# control.net
KiCad netlist of a schematic drawn in Altium Designer
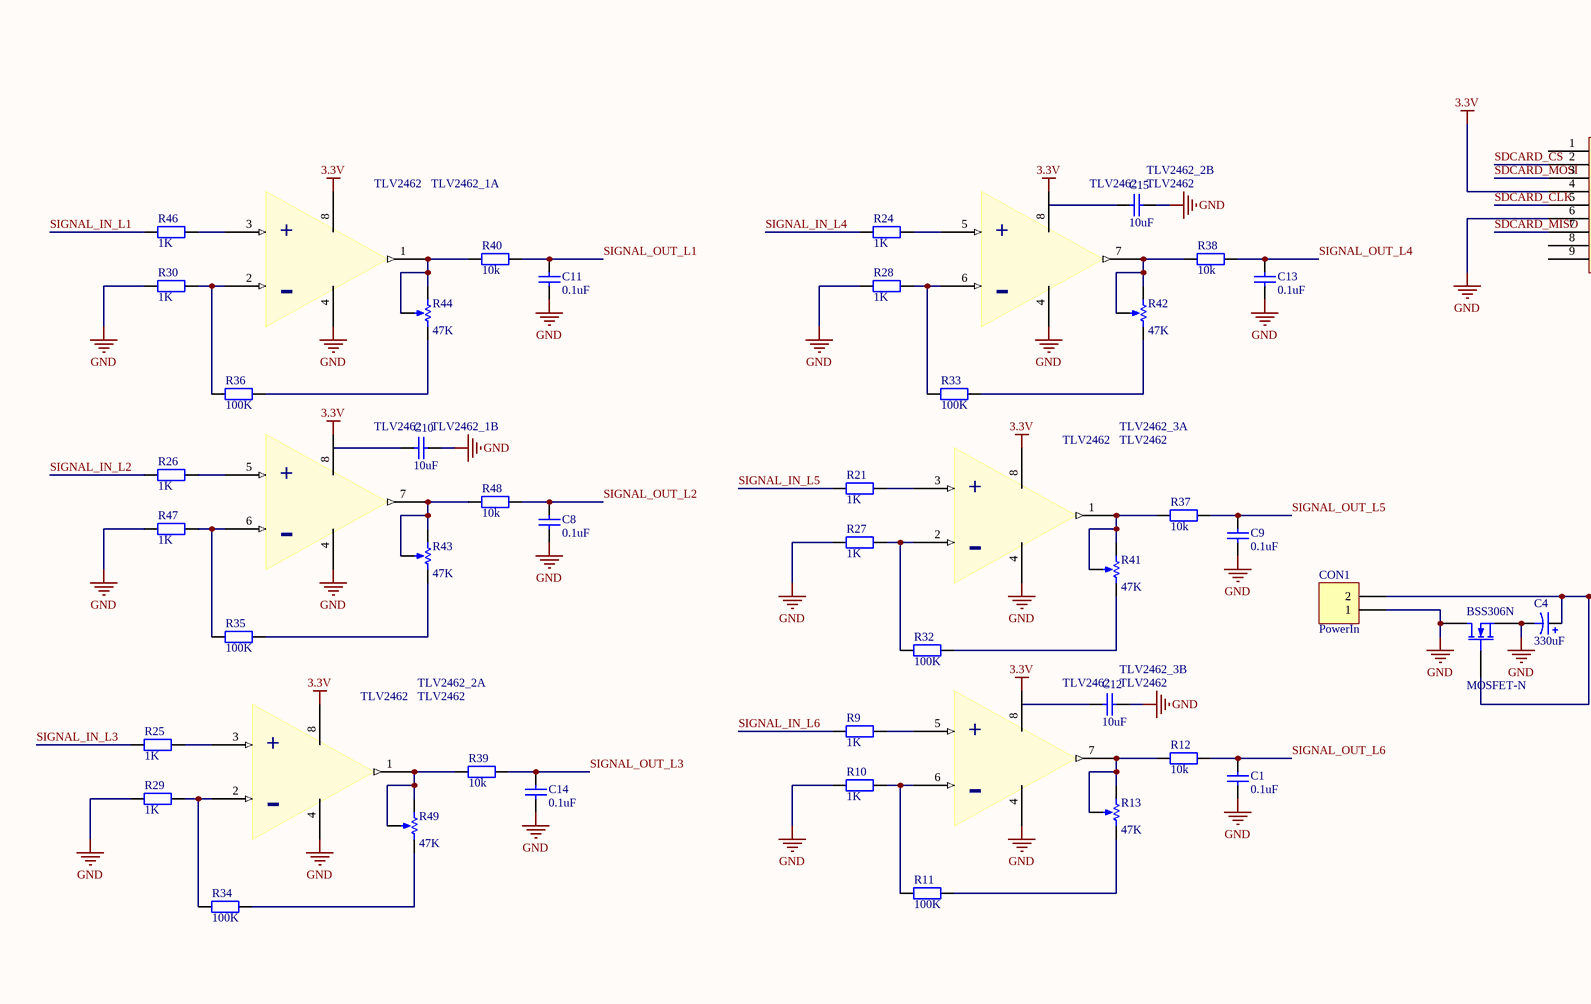
[diagram p0: control.SchDoc, top left]
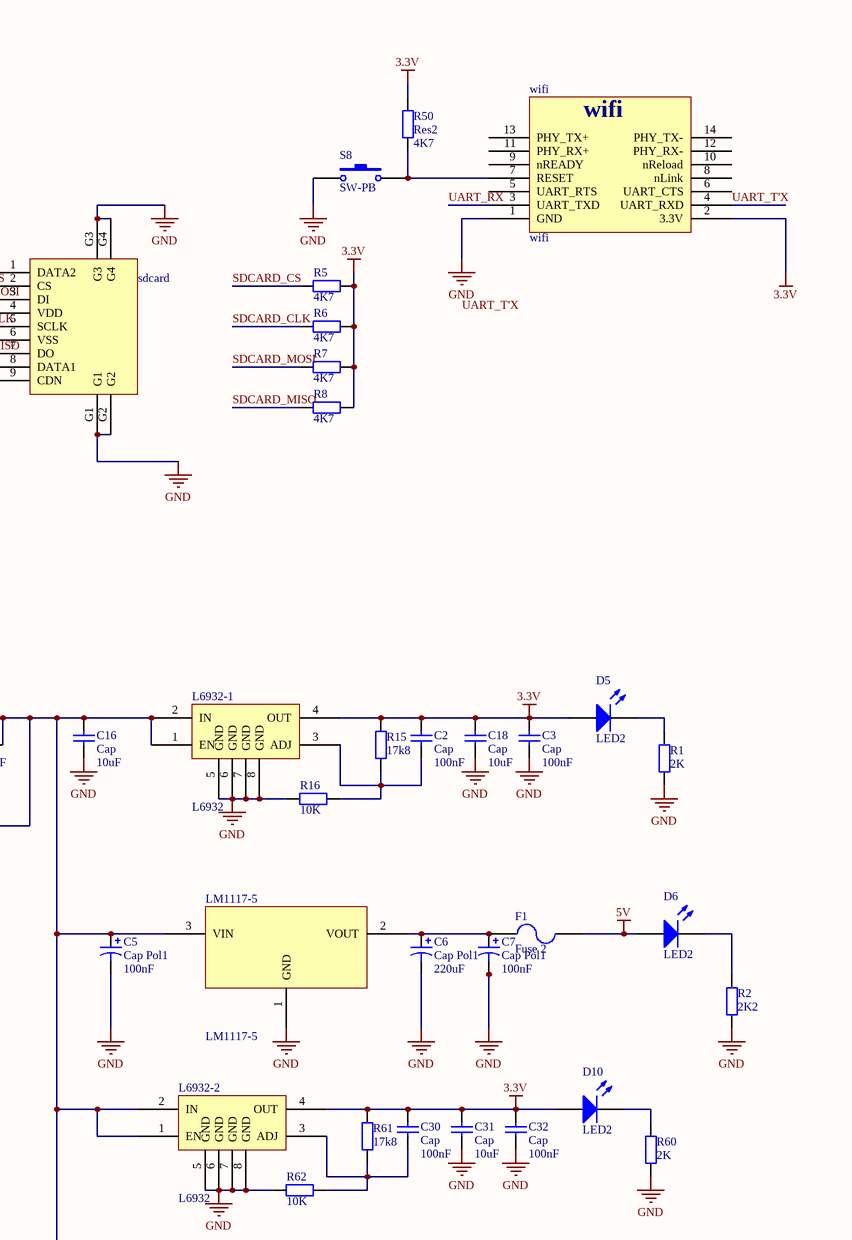
[diagram p1: control.SchDoc, top right]
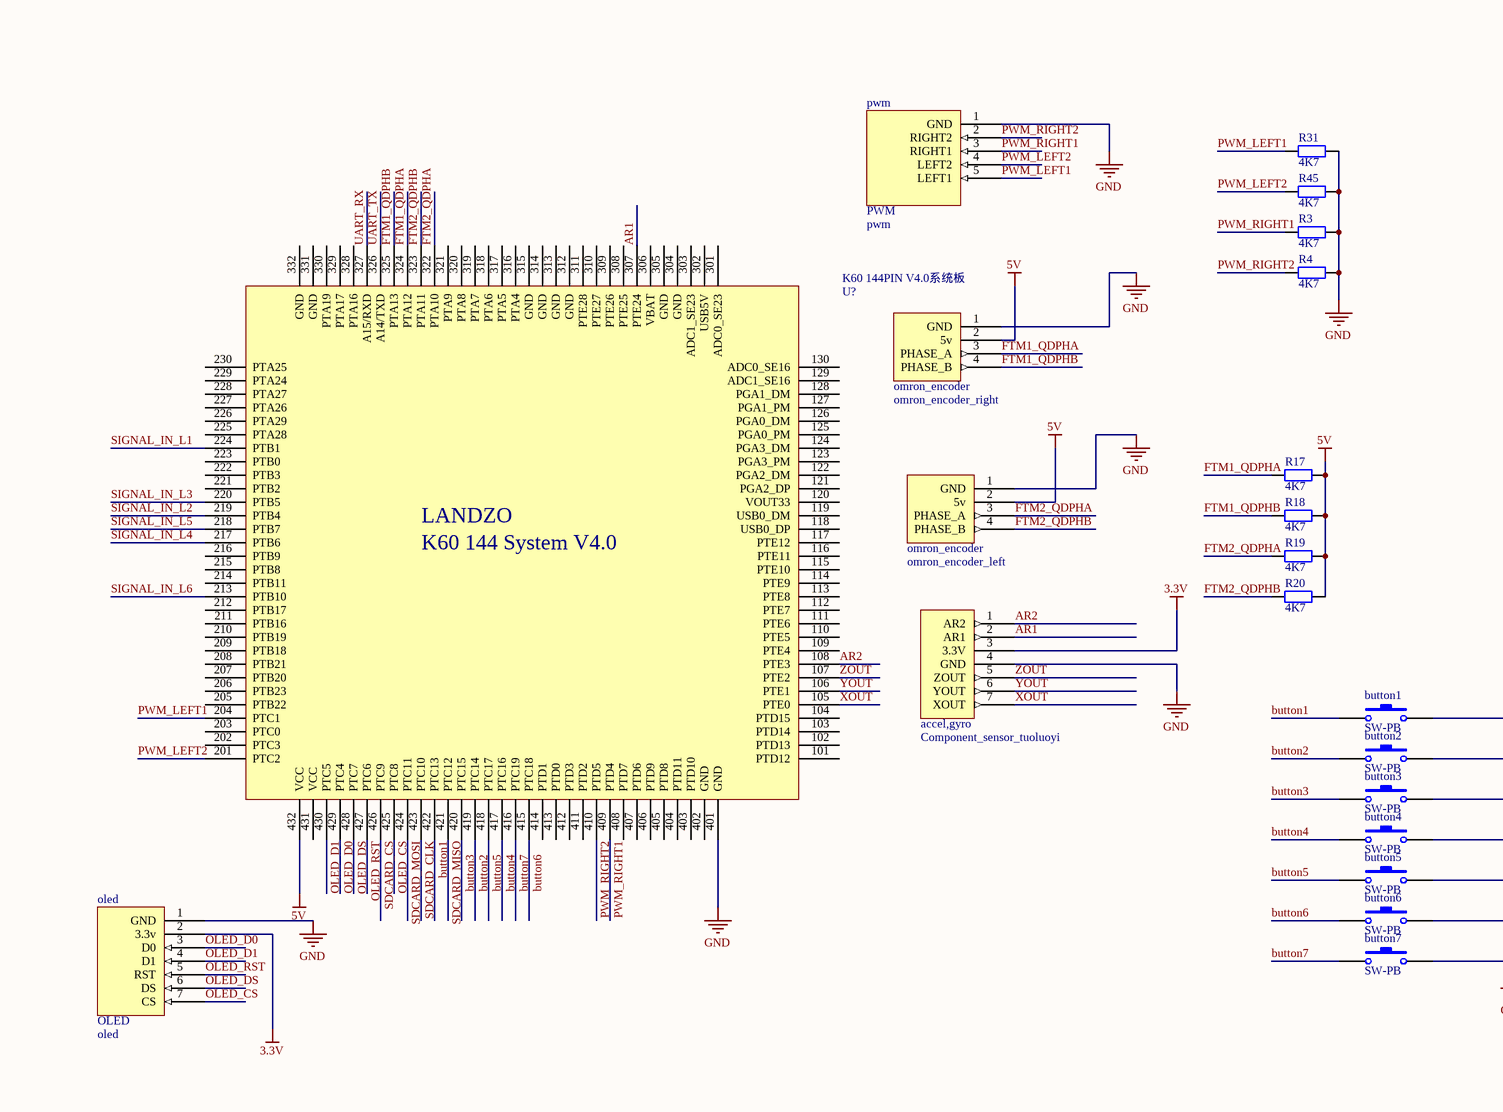
[diagram p2: control.SchDoc, bottom left]
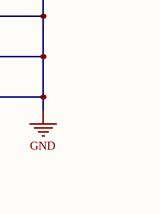
[diagram p3: control.SchDoc, bottom right]

(export (version "E")
  (design (tool "Eeschema 10.0.6"))
  (components
    (comp (ref "BSS306N")
      (value "MOSFET-N")
      (footprint "E3")
      (description "N-Channel MOSFET")
      (fields (field (name "PUBLISHER") "Altium Limited"))
      (libsource (lib "Miscellaneous Devices") (part "MOSFET-N"))
    )
    (comp (ref "button1")
      (value "SW-PB")
      (footprint "SPST-2")
      (description "Switch")
      (fields (field (name "PUBLISHER") "Altium Limited"))
      (libsource (lib "Miscellaneous Devices") (part "SW-PB"))
    )
    (comp (ref "button2")
      (value "SW-PB")
      (footprint "SPST-2")
      (description "Switch")
      (fields (field (name "PUBLISHER") "Altium Limited"))
      (libsource (lib "Miscellaneous Devices") (part "SW-PB"))
    )
    (comp (ref "button3")
      (value "SW-PB")
      (footprint "SPST-2")
      (description "Switch")
      (fields (field (name "PUBLISHER") "Altium Limited"))
      (libsource (lib "Miscellaneous Devices") (part "SW-PB"))
    )
    (comp (ref "button4")
      (value "SW-PB")
      (footprint "SPST-2")
      (description "Switch")
      (fields (field (name "PUBLISHER") "Altium Limited"))
      (libsource (lib "Miscellaneous Devices") (part "SW-PB"))
    )
    (comp (ref "button5")
      (value "SW-PB")
      (footprint "SPST-2")
      (description "Switch")
      (fields (field (name "PUBLISHER") "Altium Limited"))
      (libsource (lib "Miscellaneous Devices") (part "SW-PB"))
    )
    (comp (ref "button6")
      (value "SW-PB")
      (footprint "SPST-2")
      (description "Switch")
      (fields (field (name "PUBLISHER") "Altium Limited"))
      (libsource (lib "Miscellaneous Devices") (part "SW-PB"))
    )
    (comp (ref "button7")
      (value "SW-PB")
      (footprint "SPST-2")
      (description "Switch")
      (fields (field (name "PUBLISHER") "Altium Limited"))
      (libsource (lib "Miscellaneous Devices") (part "SW-PB"))
    )
    (comp (ref "C1")
      (value "0.1uF")
      (footprint "6-0805_M")
      (description "Capacitor")
      (fields (field (name "Comment") "Cap") (field (name "PUBLISHER") "Altium Limited"))
      (libsource (lib "Miscellaneous Devices") (part "Cap"))
    )
    (comp (ref "C2")
      (value "Cap")
      (footprint "6-0805_M")
      (description "Capacitor")
      (fields (field (name "ALTIUM_VALUE") "100nF") (field (name "PUBLISHER") "Altium Limited"))
      (libsource (lib "Miscellaneous Devices") (part "Cap"))
    )
    (comp (ref "C3")
      (value "Cap")
      (footprint "6-0805_M")
      (description "Capacitor")
      (fields (field (name "ALTIUM_VALUE") "100nF") (field (name "PUBLISHER") "Altium Limited"))
      (libsource (lib "Miscellaneous Devices") (part "Cap"))
    )
    (comp (ref "C4")
      (value "330uF")
      (footprint "RB7.6-15")
      (description "Polarized Capacitor (Radial)")
      (fields (field (name "Comment") "Cap Pol1") (field (name "PUBLISHER") "Altium Limited"))
      (libsource (lib "Miscellaneous Devices") (part "Cap Pol1"))
    )
    (comp (ref "C5")
      (value "Cap Pol1")
      (footprint "RAD-0.1")
      (description "Polarized Capacitor (Radial)")
      (fields (field (name "ALTIUM_VALUE") "100nF") (field (name "PUBLISHER") "Altium Limited"))
      (libsource (lib "Miscellaneous Devices") (part "Cap Pol1"))
    )
    (comp (ref "C6")
      (value "Cap Pol1")
      (footprint "RAD-0.1")
      (description "Polarized Capacitor (Radial)")
      (fields (field (name "ALTIUM_VALUE") "220uF") (field (name "PUBLISHER") "Altium Limited"))
      (libsource (lib "Miscellaneous Devices") (part "Cap Pol1"))
    )
    (comp (ref "C7")
      (value "Cap Pol1")
      (footprint "RAD-0.1")
      (description "Polarized Capacitor (Radial)")
      (fields (field (name "ALTIUM_VALUE") "100nF") (field (name "PUBLISHER") "Altium Limited"))
      (libsource (lib "Miscellaneous Devices") (part "Cap Pol1"))
    )
    (comp (ref "C8")
      (value "0.1uF")
      (footprint "6-0805_M")
      (description "Capacitor")
      (fields (field (name "Comment") "Cap") (field (name "PUBLISHER") "Altium Limited"))
      (libsource (lib "Miscellaneous Devices") (part "Cap"))
    )
    (comp (ref "C9")
      (value "0.1uF")
      (footprint "6-0805_M")
      (description "Capacitor")
      (fields (field (name "Comment") "Cap") (field (name "PUBLISHER") "Altium Limited"))
      (libsource (lib "Miscellaneous Devices") (part "Cap"))
    )
    (comp (ref "C10")
      (value "10uF")
      (footprint "6-0805_M")
      (description "Capacitor")
      (fields (field (name "Comment") "Cap") (field (name "PUBLISHER") "Altium Limited"))
      (libsource (lib "Miscellaneous Devices") (part "Cap"))
    )
    (comp (ref "C11")
      (value "0.1uF")
      (footprint "6-0805_M")
      (description "Capacitor")
      (fields (field (name "Comment") "Cap") (field (name "PUBLISHER") "Altium Limited"))
      (libsource (lib "Miscellaneous Devices") (part "Cap"))
    )
    (comp (ref "C12")
      (value "10uF")
      (footprint "6-0805_M")
      (description "Capacitor")
      (fields (field (name "Comment") "Cap") (field (name "PUBLISHER") "Altium Limited"))
      (libsource (lib "Miscellaneous Devices") (part "Cap"))
    )
    (comp (ref "C13")
      (value "0.1uF")
      (footprint "6-0805_M")
      (description "Capacitor")
      (fields (field (name "Comment") "Cap") (field (name "PUBLISHER") "Altium Limited"))
      (libsource (lib "Miscellaneous Devices") (part "Cap"))
    )
    (comp (ref "C14")
      (value "0.1uF")
      (footprint "6-0805_M")
      (description "Capacitor")
      (fields (field (name "Comment") "Cap") (field (name "PUBLISHER") "Altium Limited"))
      (libsource (lib "Miscellaneous Devices") (part "Cap"))
    )
    (comp (ref "C15")
      (value "10uF")
      (footprint "6-0805_M")
      (description "Capacitor")
      (fields (field (name "Comment") "Cap") (field (name "PUBLISHER") "Altium Limited"))
      (libsource (lib "Miscellaneous Devices") (part "Cap"))
    )
    (comp (ref "C16")
      (value "Cap")
      (footprint "6-0805_M")
      (description "Capacitor")
      (fields (field (name "ALTIUM_VALUE") "10uF") (field (name "PUBLISHER") "Altium Limited"))
      (libsource (lib "Miscellaneous Devices") (part "Cap"))
    )
    (comp (ref "C18")
      (value "Cap")
      (footprint "6-0805_M")
      (description "Capacitor")
      (fields (field (name "ALTIUM_VALUE") "10uF") (field (name "PUBLISHER") "Altium Limited"))
      (libsource (lib "Miscellaneous Devices") (part "Cap"))
    )
    (comp (ref "C30")
      (value "Cap")
      (footprint "6-0805_M")
      (description "Capacitor")
      (fields (field (name "ALTIUM_VALUE") "100nF") (field (name "PUBLISHER") "Altium Limited"))
      (libsource (lib "Miscellaneous Devices") (part "Cap"))
    )
    (comp (ref "C31")
      (value "Cap")
      (footprint "6-0805_M")
      (description "Capacitor")
      (fields (field (name "ALTIUM_VALUE") "10uF") (field (name "PUBLISHER") "Altium Limited"))
      (libsource (lib "Miscellaneous Devices") (part "Cap"))
    )
    (comp (ref "C32")
      (value "Cap")
      (footprint "6-0805_M")
      (description "Capacitor")
      (fields (field (name "ALTIUM_VALUE") "100nF") (field (name "PUBLISHER") "Altium Limited"))
      (libsource (lib "Miscellaneous Devices") (part "Cap"))
    )
    (comp (ref "CON1")
      (value "PowerIn")
      (description "Header, 2-Pin")
      (fields (field (name "PUBLISHER") "Altium Limited"))
      (libsource (lib "Miscellaneous Connectors") (part "Header 2"))
    )
    (comp (ref "D5")
      (value "LED2")
      (footprint "6-0805_M")
      (description "Typical RED, GREEN, YELLOW, AMBER GaAs LED")
      (fields (field (name "PUBLISHER") "Altium Limited"))
      (libsource (lib "Miscellaneous Devices") (part "LED2"))
    )
    (comp (ref "D6")
      (value "LED2")
      (footprint "6-0805_M")
      (description "Typical RED, GREEN, YELLOW, AMBER GaAs LED")
      (fields (field (name "PUBLISHER") "Altium Limited"))
      (libsource (lib "Miscellaneous Devices") (part "LED2"))
    )
    (comp (ref "D10")
      (value "LED2")
      (footprint "6-0805_M")
      (description "Typical RED, GREEN, YELLOW, AMBER GaAs LED")
      (fields (field (name "PUBLISHER") "Altium Limited"))
      (libsource (lib "Miscellaneous Devices") (part "LED2"))
    )
    (comp (ref "F1")
      (value "Fuse 2")
      (footprint "PIN-W2/E2.8")
      (description "Fuse")
      (fields (field (name "PUBLISHER") "Altium Limited"))
      (libsource (lib "Miscellaneous Devices") (part "Fuse 2"))
    )
    (comp (ref "K60 144PIN V4.0系统板")
      (value "U?")
      (footprint "K60_Board")
      (libsource (lib "最小系统板K60P144-V4.0") (part "K60 144PIN V4.0系统板"))
    )
    (comp (ref "L6932-1")
      (value "L6932")
      (footprint "L6932")
      (libsource (lib "Schlib_k60_core") (part "L6932"))
    )
    (comp (ref "L6932-2")
      (value "L6932")
      (footprint "L6932")
      (libsource (lib "Schlib_k60_core") (part "L6932"))
    )
    (comp (ref "LM1117-5")
      (value "LM1117-5")
      (footprint "SOT223_M")
      (libsource (lib "Schlib_k60_core") (part "LM1117-5"))
    )
    (comp (ref "oled") (value "oled") (footprint "HDR1X7H") (libsource (lib "Schlib_k60_core") (part "oled")))
    (comp (ref "omron_encoder_left")
      (value "omron_encoder")
      (footprint "HDR1X4H")
      (libsource (lib "Schlib_k60_core") (part "omron_encoder"))
    )
    (comp (ref "omron_encoder_right")
      (value "omron_encoder")
      (footprint "HDR1X4")
      (libsource (lib "Schlib_k60_core") (part "omron_encoder"))
    )
    (comp (ref "pwm") (value "pwm") (footprint "HDR1X5H") (libsource (lib "Schlib_k60_core") (part "pwm")))
    (comp (ref "R1")
      (value "2K")
      (footprint "6-0805_M")
      (description "Resistor")
      (fields (field (name "Comment") "Res2") (field (name "PUBLISHER") "Altium Limited"))
      (libsource (lib "") (part "Res2_1"))
    )
    (comp (ref "R2")
      (value "2K2")
      (footprint "6-0805_M")
      (description "Resistor")
      (fields (field (name "Comment") "Res2") (field (name "PUBLISHER") "Altium Limited"))
      (libsource (lib "") (part "Res2_1"))
    )
    (comp (ref "R3")
      (value "4K7")
      (footprint "6-0805_M")
      (description "Resistor")
      (fields (field (name "Comment") "Res2") (field (name "PUBLISHER") "Altium Limited"))
      (libsource (lib "Miscellaneous Devices") (part "Res2"))
    )
    (comp (ref "R4")
      (value "4K7")
      (footprint "6-0805_M")
      (description "Resistor")
      (fields (field (name "Comment") "Res2") (field (name "PUBLISHER") "Altium Limited"))
      (libsource (lib "Miscellaneous Devices") (part "Res2"))
    )
    (comp (ref "R5")
      (value "4K7")
      (footprint "6-0805_M")
      (description "Resistor")
      (fields (field (name "Comment") "Res2") (field (name "PUBLISHER") "Altium Limited"))
      (libsource (lib "Miscellaneous Devices") (part "Res2"))
    )
    (comp (ref "R6")
      (value "4K7")
      (footprint "6-0805_M")
      (description "Resistor")
      (fields (field (name "Comment") "Res2") (field (name "PUBLISHER") "Altium Limited"))
      (libsource (lib "Miscellaneous Devices") (part "Res2"))
    )
    (comp (ref "R7")
      (value "4K7")
      (footprint "6-0805_M")
      (description "Resistor")
      (fields (field (name "Comment") "Res2") (field (name "PUBLISHER") "Altium Limited"))
      (libsource (lib "Miscellaneous Devices") (part "Res2"))
    )
    (comp (ref "R8")
      (value "4K7")
      (footprint "6-0805_M")
      (description "Resistor")
      (fields (field (name "Comment") "Res2") (field (name "PUBLISHER") "Altium Limited"))
      (libsource (lib "Miscellaneous Devices") (part "Res2"))
    )
    (comp (ref "R9")
      (value "1K")
      (footprint "6-0805_M")
      (description "Resistor")
      (fields (field (name "Comment") "Res2") (field (name "PUBLISHER") "Altium Limited"))
      (libsource (lib "Miscellaneous Devices") (part "Res2"))
    )
    (comp (ref "R10")
      (value "1K")
      (footprint "6-0805_M")
      (description "Resistor")
      (fields (field (name "Comment") "Res2") (field (name "PUBLISHER") "Altium Limited"))
      (libsource (lib "Miscellaneous Devices") (part "Res2"))
    )
    (comp (ref "R11")
      (value "100K")
      (footprint "6-0805_M")
      (description "Resistor")
      (fields (field (name "Comment") "Res2") (field (name "PUBLISHER") "Altium Limited"))
      (libsource (lib "Miscellaneous Devices") (part "Res2"))
    )
    (comp (ref "R12")
      (value "10k")
      (footprint "6-0805_M")
      (description "Resistor")
      (fields (field (name "Comment") "Res2") (field (name "PUBLISHER") "Altium Limited"))
      (libsource (lib "Miscellaneous Devices") (part "Res2"))
    )
    (comp (ref "R13")
      (value "47K")
      (footprint "VR5")
      (description "Potentiometer")
      (fields (field (name "Comment") "R4") (field (name "PUBLISHER") "Altium Limited"))
      (libsource (lib "Miscellaneous Devices") (part "RPot"))
    )
    (comp (ref "R15")
      (value "17k8")
      (footprint "6-0805_M")
      (description "Resistor")
      (fields (field (name "Comment") "Res2") (field (name "PUBLISHER") "Altium Limited"))
      (libsource (lib "") (part "Res2_1"))
    )
    (comp (ref "R16")
      (value "10K")
      (footprint "6-0805_M")
      (description "Resistor")
      (fields (field (name "Comment") "Res2") (field (name "PUBLISHER") "Altium Limited"))
      (libsource (lib "Miscellaneous Devices") (part "Res2"))
    )
    (comp (ref "R17")
      (value "4K7")
      (footprint "6-0805_M")
      (description "Resistor")
      (fields (field (name "Comment") "Res2") (field (name "PUBLISHER") "Altium Limited"))
      (libsource (lib "Miscellaneous Devices") (part "Res2"))
    )
    (comp (ref "R18")
      (value "4K7")
      (footprint "6-0805_M")
      (description "Resistor")
      (fields (field (name "Comment") "Res2") (field (name "PUBLISHER") "Altium Limited"))
      (libsource (lib "Miscellaneous Devices") (part "Res2"))
    )
    (comp (ref "R19")
      (value "4K7")
      (footprint "6-0805_M")
      (description "Resistor")
      (fields (field (name "Comment") "Res2") (field (name "PUBLISHER") "Altium Limited"))
      (libsource (lib "Miscellaneous Devices") (part "Res2"))
    )
    (comp (ref "R20")
      (value "4K7")
      (footprint "6-0805_M")
      (description "Resistor")
      (fields (field (name "Comment") "Res2") (field (name "PUBLISHER") "Altium Limited"))
      (libsource (lib "Miscellaneous Devices") (part "Res2"))
    )
    (comp (ref "R21")
      (value "1K")
      (footprint "6-0805_M")
      (description "Resistor")
      (fields (field (name "Comment") "Res2") (field (name "PUBLISHER") "Altium Limited"))
      (libsource (lib "Miscellaneous Devices") (part "Res2"))
    )
    (comp (ref "R24")
      (value "1K")
      (footprint "6-0805_M")
      (description "Resistor")
      (fields (field (name "Comment") "Res2") (field (name "PUBLISHER") "Altium Limited"))
      (libsource (lib "Miscellaneous Devices") (part "Res2"))
    )
    (comp (ref "R25")
      (value "1K")
      (footprint "6-0805_M")
      (description "Resistor")
      (fields (field (name "Comment") "Res2") (field (name "PUBLISHER") "Altium Limited"))
      (libsource (lib "Miscellaneous Devices") (part "Res2"))
    )
    (comp (ref "R26")
      (value "1K")
      (footprint "6-0805_M")
      (description "Resistor")
      (fields (field (name "Comment") "Res2") (field (name "PUBLISHER") "Altium Limited"))
      (libsource (lib "Miscellaneous Devices") (part "Res2"))
    )
    (comp (ref "R27")
      (value "1K")
      (footprint "6-0805_M")
      (description "Resistor")
      (fields (field (name "Comment") "Res2") (field (name "PUBLISHER") "Altium Limited"))
      (libsource (lib "Miscellaneous Devices") (part "Res2"))
    )
    (comp (ref "R28")
      (value "1K")
      (footprint "6-0805_M")
      (description "Resistor")
      (fields (field (name "Comment") "Res2") (field (name "PUBLISHER") "Altium Limited"))
      (libsource (lib "Miscellaneous Devices") (part "Res2"))
    )
    (comp (ref "R29")
      (value "1K")
      (footprint "6-0805_M")
      (description "Resistor")
      (fields (field (name "Comment") "Res2") (field (name "PUBLISHER") "Altium Limited"))
      (libsource (lib "Miscellaneous Devices") (part "Res2"))
    )
    (comp (ref "R30")
      (value "1K")
      (footprint "6-0805_M")
      (description "Resistor")
      (fields (field (name "Comment") "Res2") (field (name "PUBLISHER") "Altium Limited"))
      (libsource (lib "Miscellaneous Devices") (part "Res2"))
    )
    (comp (ref "R31")
      (value "4K7")
      (footprint "6-0805_M")
      (description "Resistor")
      (fields (field (name "Comment") "Res2") (field (name "PUBLISHER") "Altium Limited"))
      (libsource (lib "Miscellaneous Devices") (part "Res2"))
    )
    (comp (ref "R32")
      (value "100K")
      (footprint "6-0805_M")
      (description "Resistor")
      (fields (field (name "Comment") "Res2") (field (name "PUBLISHER") "Altium Limited"))
      (libsource (lib "Miscellaneous Devices") (part "Res2"))
    )
    (comp (ref "R33")
      (value "100K")
      (footprint "6-0805_M")
      (description "Resistor")
      (fields (field (name "Comment") "Res2") (field (name "PUBLISHER") "Altium Limited"))
      (libsource (lib "Miscellaneous Devices") (part "Res2"))
    )
    (comp (ref "R34")
      (value "100K")
      (footprint "6-0805_M")
      (description "Resistor")
      (fields (field (name "Comment") "Res2") (field (name "PUBLISHER") "Altium Limited"))
      (libsource (lib "Miscellaneous Devices") (part "Res2"))
    )
    (comp (ref "R35")
      (value "100K")
      (footprint "6-0805_M")
      (description "Resistor")
      (fields (field (name "Comment") "Res2") (field (name "PUBLISHER") "Altium Limited"))
      (libsource (lib "Miscellaneous Devices") (part "Res2"))
    )
    (comp (ref "R36")
      (value "100K")
      (footprint "6-0805_M")
      (description "Resistor")
      (fields (field (name "Comment") "Res2") (field (name "PUBLISHER") "Altium Limited"))
      (libsource (lib "Miscellaneous Devices") (part "Res2"))
    )
    (comp (ref "R37")
      (value "10k")
      (footprint "6-0805_M")
      (description "Resistor")
      (fields (field (name "Comment") "Res2") (field (name "PUBLISHER") "Altium Limited"))
      (libsource (lib "Miscellaneous Devices") (part "Res2"))
    )
    (comp (ref "R38")
      (value "10k")
      (footprint "6-0805_M")
      (description "Resistor")
      (fields (field (name "Comment") "Res2") (field (name "PUBLISHER") "Altium Limited"))
      (libsource (lib "Miscellaneous Devices") (part "Res2"))
    )
    (comp (ref "R39")
      (value "10k")
      (footprint "6-0805_M")
      (description "Resistor")
      (fields (field (name "Comment") "Res2") (field (name "PUBLISHER") "Altium Limited"))
      (libsource (lib "Miscellaneous Devices") (part "Res2"))
    )
    (comp (ref "R40")
      (value "10k")
      (footprint "6-0805_M")
      (description "Resistor")
      (fields (field (name "Comment") "Res2") (field (name "PUBLISHER") "Altium Limited"))
      (libsource (lib "Miscellaneous Devices") (part "Res2"))
    )
    (comp (ref "R41")
      (value "47K")
      (footprint "VR5")
      (description "Potentiometer")
      (fields (field (name "Comment") "R4") (field (name "PUBLISHER") "Altium Limited"))
      (libsource (lib "Miscellaneous Devices") (part "RPot"))
    )
    (comp (ref "R42")
      (value "47K")
      (footprint "VR5")
      (description "Potentiometer")
      (fields (field (name "Comment") "R4") (field (name "PUBLISHER") "Altium Limited"))
      (libsource (lib "Miscellaneous Devices") (part "RPot"))
    )
    (comp (ref "R43")
      (value "47K")
      (footprint "VR5")
      (description "Potentiometer")
      (fields (field (name "Comment") "R4") (field (name "PUBLISHER") "Altium Limited"))
      (libsource (lib "Miscellaneous Devices") (part "RPot"))
    )
    (comp (ref "R44")
      (value "47K")
      (footprint "VR5")
      (description "Potentiometer")
      (fields (field (name "Comment") "R4") (field (name "PUBLISHER") "Altium Limited"))
      (libsource (lib "Miscellaneous Devices") (part "RPot"))
    )
    (comp (ref "R45")
      (value "4K7")
      (footprint "6-0805_M")
      (description "Resistor")
      (fields (field (name "Comment") "Res2") (field (name "PUBLISHER") "Altium Limited"))
      (libsource (lib "Miscellaneous Devices") (part "Res2"))
    )
    (comp (ref "R46")
      (value "1K")
      (footprint "6-0805_M")
      (description "Resistor")
      (fields (field (name "Comment") "Res2") (field (name "PUBLISHER") "Altium Limited"))
      (libsource (lib "Miscellaneous Devices") (part "Res2"))
    )
    (comp (ref "R47")
      (value "1K")
      (footprint "6-0805_M")
      (description "Resistor")
      (fields (field (name "Comment") "Res2") (field (name "PUBLISHER") "Altium Limited"))
      (libsource (lib "Miscellaneous Devices") (part "Res2"))
    )
    (comp (ref "R48")
      (value "10k")
      (footprint "6-0805_M")
      (description "Resistor")
      (fields (field (name "Comment") "Res2") (field (name "PUBLISHER") "Altium Limited"))
      (libsource (lib "Miscellaneous Devices") (part "Res2"))
    )
    (comp (ref "R49")
      (value "47K")
      (footprint "VR5")
      (description "Potentiometer")
      (fields (field (name "Comment") "R4") (field (name "PUBLISHER") "Altium Limited"))
      (libsource (lib "Miscellaneous Devices") (part "RPot"))
    )
    (comp (ref "R50")
      (value "Res2")
      (footprint "6-0805_M")
      (description "Resistor")
      (fields (field (name "ALTIUM_VALUE") "4K7") (field (name "PUBLISHER") "Altium Limited"))
      (libsource (lib "") (part "Res2_1"))
    )
    (comp (ref "R60")
      (value "2K")
      (footprint "6-0805_M")
      (description "Resistor")
      (fields (field (name "Comment") "Res2") (field (name "PUBLISHER") "Altium Limited"))
      (libsource (lib "") (part "Res2_1"))
    )
    (comp (ref "R61")
      (value "17k8")
      (footprint "6-0805_M")
      (description "Resistor")
      (fields (field (name "Comment") "Res2") (field (name "PUBLISHER") "Altium Limited"))
      (libsource (lib "") (part "Res2_1"))
    )
    (comp (ref "R62")
      (value "10K")
      (footprint "6-0805_M")
      (description "Resistor")
      (fields (field (name "Comment") "Res2") (field (name "PUBLISHER") "Altium Limited"))
      (libsource (lib "Miscellaneous Devices") (part "Res2"))
    )
    (comp (ref "S8")
      (value "SW-PB")
      (footprint "SPST-2")
      (description "Switch")
      (fields (field (name "PUBLISHER") "Altium Limited"))
      (libsource (lib "Miscellaneous Devices") (part "SW-PB"))
    )
    (comp (ref "sdcard") (value "sdcard") (libsource (lib "Schlib_k60_core") (part "sdcard")))
    (comp (ref "sensor_tuoluoyi")
      (value "Component_sensor_tuoluoyi")
      (footprint "HDR1X7")
      (libsource (lib "Schlib_k60_core") (part "Component_sensor_tuoluoyi"))
    )
    (comp (ref "TLV2462_1")
      (value "TLV2462")
      (footprint "SOP127P600X175-8L")
      (libsource (lib "Schlib_k60_core") (part "TLV2462"))
    )
    (comp (ref "TLV2462_2")
      (value "TLV2462")
      (footprint "SOP127P600X175-8L")
      (libsource (lib "Schlib_k60_core") (part "TLV2462"))
    )
    (comp (ref "TLV2462_3")
      (value "TLV2462")
      (footprint "SOP127P600X175-8L")
      (libsource (lib "Schlib_k60_core") (part "TLV2462"))
    )
    (comp (ref "wifi") (value "wifi") (libsource (lib "Schlib_k60_core") (part "wifi")))
  )
  (nets
    (net (code "1") (name "/AR1") (class "Default")
      (node (ref "K60 144PIN V4.0系统板") (pin "307") (pinfunction "PTE24_307") (pintype "passive"))
      (node (ref "sensor_tuoluoyi") (pin "2") (pinfunction "AR1_2") (pintype "output"))
    )
    (net (code "2") (name "/AR2") (class "Default")
      (node (ref "K60 144PIN V4.0系统板") (pin "108") (pinfunction "PTE3_108") (pintype "passive"))
      (node (ref "sensor_tuoluoyi") (pin "1") (pinfunction "AR2_1") (pintype "output"))
    )
    (net (code "3") (name "/FTM1_QDPHA") (class "Default")
      (node (ref "K60 144PIN V4.0系统板") (pin "324") (pinfunction "PTA12_324") (pintype "passive"))
      (node (ref "R17") (pin "1") (pinfunction "1_1") (pintype "passive"))
      (node (ref "omron_encoder_right") (pin "3") (pinfunction "PHASE_A_3") (pintype "output"))
    )
    (net (code "4") (name "/FTM1_QDPHB") (class "Default")
      (node (ref "K60 144PIN V4.0系统板") (pin "325") (pinfunction "PTA13_325") (pintype "passive"))
      (node (ref "R18") (pin "1") (pinfunction "1_1") (pintype "passive"))
      (node (ref "omron_encoder_right") (pin "4") (pinfunction "PHASE_B_4") (pintype "output"))
    )
    (net (code "5") (name "/FTM2_QDPHA") (class "Default")
      (node (ref "K60 144PIN V4.0系统板") (pin "322") (pinfunction "PTA10_322") (pintype "passive"))
      (node (ref "R19") (pin "1") (pinfunction "1_1") (pintype "passive"))
      (node (ref "omron_encoder_left") (pin "3") (pinfunction "PHASE_A_3") (pintype "output"))
    )
    (net (code "6") (name "/FTM2_QDPHB") (class "Default")
      (node (ref "K60 144PIN V4.0系统板") (pin "323") (pinfunction "PTA11_323") (pintype "passive"))
      (node (ref "R20") (pin "1") (pinfunction "1_1") (pintype "passive"))
      (node (ref "omron_encoder_left") (pin "4") (pinfunction "PHASE_B_4") (pintype "output"))
    )
    (net (code "7") (name "/OLED_CS") (class "Default")
      (node (ref "K60 144PIN V4.0系统板") (pin "425") (pinfunction "PTC8_425") (pintype "passive"))
      (node (ref "oled") (pin "7") (pinfunction "CS_7") (pintype "input"))
    )
    (net (code "8") (name "/OLED_D0") (class "Default")
      (node (ref "K60 144PIN V4.0系统板") (pin "429") (pinfunction "PTC4_429") (pintype "passive"))
      (node (ref "oled") (pin "3") (pinfunction "D0_3") (pintype "input"))
    )
    (net (code "9") (name "/OLED_D1") (class "Default")
      (node (ref "K60 144PIN V4.0系统板") (pin "430") (pinfunction "PTC5_430") (pintype "passive"))
      (node (ref "oled") (pin "4") (pinfunction "D1_4") (pintype "input"))
    )
    (net (code "10") (name "/OLED_DS") (class "Default")
      (node (ref "K60 144PIN V4.0系统板") (pin "428") (pinfunction "PTC7_428") (pintype "passive"))
      (node (ref "oled") (pin "6") (pinfunction "DS_6") (pintype "input"))
    )
    (net (code "11") (name "/OLED_RST") (class "Default")
      (node (ref "K60 144PIN V4.0系统板") (pin "427") (pinfunction "PTC6_427") (pintype "passive"))
      (node (ref "oled") (pin "5") (pinfunction "RST_5") (pintype "input"))
    )
    (net (code "12") (name "/PWM_LEFT1") (class "Default")
      (node (ref "K60 144PIN V4.0系统板") (pin "204") (pinfunction "PTC1_204") (pintype "passive"))
      (node (ref "R31") (pin "1") (pinfunction "1_1") (pintype "passive"))
      (node (ref "pwm") (pin "5") (pinfunction "LEFT1_5") (pintype "input"))
    )
    (net (code "13") (name "/PWM_LEFT2") (class "Default")
      (node (ref "K60 144PIN V4.0系统板") (pin "201") (pinfunction "PTC2_201") (pintype "passive"))
      (node (ref "R45") (pin "1") (pinfunction "1_1") (pintype "passive"))
      (node (ref "pwm") (pin "4") (pinfunction "LEFT2_4") (pintype "input"))
    )
    (net (code "14") (name "/PWM_RIGHT1") (class "Default")
      (node (ref "K60 144PIN V4.0系统板") (pin "409") (pinfunction "PTD4_409") (pintype "passive"))
      (node (ref "R3") (pin "1") (pinfunction "1_1") (pintype "passive"))
      (node (ref "pwm") (pin "3") (pinfunction "RIGHT1_3") (pintype "input"))
    )
    (net (code "15") (name "/PWM_RIGHT2") (class "Default")
      (node (ref "K60 144PIN V4.0系统板") (pin "410") (pinfunction "PTD5_410") (pintype "passive"))
      (node (ref "R4") (pin "1") (pinfunction "1_1") (pintype "passive"))
      (node (ref "pwm") (pin "2") (pinfunction "RIGHT2_2") (pintype "input"))
    )
    (net (code "16") (name "/SDCARD_CLK") (class "Default")
      (node (ref "K60 144PIN V4.0系统板") (pin "423") (pinfunction "PTC10_423") (pintype "passive"))
      (node (ref "R6") (pin "1") (pinfunction "1_1") (pintype "passive"))
      (node (ref "sdcard") (pin "5") (pinfunction "SCLK_5") (pintype "power_in"))
    )
    (net (code "17") (name "/SDCARD_CS") (class "Default")
      (node (ref "K60 144PIN V4.0系统板") (pin "426") (pinfunction "PTC9_426") (pintype "passive"))
      (node (ref "R5") (pin "1") (pinfunction "1_1") (pintype "passive"))
      (node (ref "sdcard") (pin "2") (pinfunction "CS_2") (pintype "power_in"))
    )
    (net (code "18") (name "/SDCARD_MISO") (class "Default")
      (node (ref "K60 144PIN V4.0系统板") (pin "421") (pinfunction "PTC12_421") (pintype "passive"))
      (node (ref "R8") (pin "1") (pinfunction "1_1") (pintype "passive"))
      (node (ref "sdcard") (pin "7") (pinfunction "DO_7") (pintype "power_in"))
    )
    (net (code "19") (name "/SDCARD_MOSI") (class "Default")
      (node (ref "K60 144PIN V4.0系统板") (pin "424") (pinfunction "PTC11_424") (pintype "passive"))
      (node (ref "R7") (pin "1") (pinfunction "1_1") (pintype "passive"))
      (node (ref "sdcard") (pin "3") (pinfunction "DI_3") (pintype "power_in"))
    )
    (net (code "20") (name "/SIGNAL_IN_L1") (class "Default")
      (node (ref "K60 144PIN V4.0系统板") (pin "224") (pinfunction "PTB1_224") (pintype "passive"))
      (node (ref "R46") (pin "1") (pinfunction "1_1") (pintype "passive"))
    )
    (net (code "21") (name "/SIGNAL_IN_L2") (class "Default")
      (node (ref "K60 144PIN V4.0系统板") (pin "219") (pinfunction "PTB4_219") (pintype "passive"))
      (node (ref "R26") (pin "1") (pinfunction "1_1") (pintype "passive"))
    )
    (net (code "22") (name "/SIGNAL_IN_L3") (class "Default")
      (node (ref "K60 144PIN V4.0系统板") (pin "220") (pinfunction "PTB5_220") (pintype "passive"))
      (node (ref "R25") (pin "1") (pinfunction "1_1") (pintype "passive"))
    )
    (net (code "23") (name "/SIGNAL_IN_L4") (class "Default")
      (node (ref "K60 144PIN V4.0系统板") (pin "217") (pinfunction "PTB6_217") (pintype "passive"))
      (node (ref "R24") (pin "1") (pinfunction "1_1") (pintype "passive"))
    )
    (net (code "24") (name "/SIGNAL_IN_L5") (class "Default")
      (node (ref "K60 144PIN V4.0系统板") (pin "218") (pinfunction "PTB7_218") (pintype "passive"))
      (node (ref "R21") (pin "1") (pinfunction "1_1") (pintype "passive"))
    )
    (net (code "25") (name "/SIGNAL_IN_L6") (class "Default")
      (node (ref "K60 144PIN V4.0系统板") (pin "213") (pinfunction "PTB10_213") (pintype "passive"))
      (node (ref "R9") (pin "1") (pinfunction "1_1") (pintype "passive"))
    )
    (net (code "26") (name "/SIGNAL_OUT_L1") (class "Default")
      (node (ref "C11") (pin "2") (pinfunction "2_2") (pintype "passive"))
      (node (ref "R40") (pin "2") (pinfunction "2_2") (pintype "passive"))
    )
    (net (code "27") (name "/SIGNAL_OUT_L2") (class "Default")
      (node (ref "C8") (pin "2") (pinfunction "2_2") (pintype "passive"))
      (node (ref "R48") (pin "2") (pinfunction "2_2") (pintype "passive"))
    )
    (net (code "28") (name "/SIGNAL_OUT_L3") (class "Default")
      (node (ref "C14") (pin "2") (pinfunction "2_2") (pintype "passive"))
      (node (ref "R39") (pin "2") (pinfunction "2_2") (pintype "passive"))
    )
    (net (code "29") (name "/SIGNAL_OUT_L4") (class "Default")
      (node (ref "C13") (pin "2") (pinfunction "2_2") (pintype "passive"))
      (node (ref "R38") (pin "2") (pinfunction "2_2") (pintype "passive"))
    )
    (net (code "30") (name "/SIGNAL_OUT_L5") (class "Default")
      (node (ref "C9") (pin "2") (pinfunction "2_2") (pintype "passive"))
      (node (ref "R37") (pin "2") (pinfunction "2_2") (pintype "passive"))
    )
    (net (code "31") (name "/SIGNAL_OUT_L6") (class "Default")
      (node (ref "C1") (pin "2") (pinfunction "2_2") (pintype "passive"))
      (node (ref "R12") (pin "2") (pinfunction "2_2") (pintype "passive"))
    )
    (net (code "32") (name "/UART_RX") (class "Default")
      (node (ref "K60 144PIN V4.0系统板") (pin "327") (pinfunction "A15/RXD_327") (pintype "passive"))
      (node (ref "wifi") (pin "3") (pinfunction "UART_TXD_3") (pintype "power_in"))
    )
    (net (code "33") (name "/UART_T'X") (class "Default")
      (node (ref "wifi") (pin "4") (pinfunction "UART_RXD_4") (pintype "power_in"))
    )
    (net (code "34") (name "/UART_TX") (class "Default")
      (node (ref "K60 144PIN V4.0系统板") (pin "326") (pinfunction "A14/TXD_326") (pintype "passive"))
    )
    (net (code "35") (name "/XOUT") (class "Default")
      (node (ref "K60 144PIN V4.0系统板") (pin "105") (pinfunction "PTE0_105") (pintype "passive"))
      (node (ref "sensor_tuoluoyi") (pin "7") (pinfunction "XOUT_7") (pintype "output"))
    )
    (net (code "36") (name "/YOUT") (class "Default")
      (node (ref "K60 144PIN V4.0系统板") (pin "106") (pinfunction "PTE1_106") (pintype "passive"))
      (node (ref "sensor_tuoluoyi") (pin "6") (pinfunction "YOUT_6") (pintype "output"))
    )
    (net (code "37") (name "/ZOUT") (class "Default")
      (node (ref "K60 144PIN V4.0系统板") (pin "107") (pinfunction "PTE2_107") (pintype "passive"))
      (node (ref "sensor_tuoluoyi") (pin "5") (pinfunction "ZOUT_5") (pintype "output"))
    )
    (net (code "38") (name "/button1") (class "Default")
      (node (ref "K60 144PIN V4.0系统板") (pin "422") (pinfunction "PTC13_422") (pintype "passive"))
      (node (ref "button1") (pin "1") (pinfunction "1_1") (pintype "passive"))
    )
    (net (code "39") (name "/button2") (class "Default")
      (node (ref "K60 144PIN V4.0系统板") (pin "419") (pinfunction "PTC14_419") (pintype "passive"))
      (node (ref "button2") (pin "1") (pinfunction "1_1") (pintype "passive"))
    )
    (net (code "40") (name "/button3") (class "Default")
      (node (ref "K60 144PIN V4.0系统板") (pin "420") (pinfunction "PTC15_420") (pintype "passive"))
      (node (ref "button3") (pin "1") (pinfunction "1_1") (pintype "passive"))
    )
    (net (code "41") (name "/button4") (class "Default")
      (node (ref "K60 144PIN V4.0系统板") (pin "417") (pinfunction "PTC16_417") (pintype "passive"))
      (node (ref "button4") (pin "1") (pinfunction "1_1") (pintype "passive"))
    )
    (net (code "42") (name "/button5") (class "Default")
      (node (ref "K60 144PIN V4.0系统板") (pin "418") (pinfunction "PTC17_418") (pintype "passive"))
      (node (ref "button5") (pin "1") (pinfunction "1_1") (pintype "passive"))
    )
    (net (code "43") (name "/button6") (class "Default")
      (node (ref "K60 144PIN V4.0系统板") (pin "415") (pinfunction "PTC18_415") (pintype "passive"))
      (node (ref "button6") (pin "1") (pinfunction "1_1") (pintype "passive"))
    )
    (net (code "44") (name "/button7") (class "Default")
      (node (ref "K60 144PIN V4.0系统板") (pin "416") (pinfunction "PTC19_416") (pintype "passive"))
      (node (ref "button7") (pin "1") (pinfunction "1_1") (pintype "passive"))
    )
    (net (code "45") (name "3.3V") (class "Default")
      (node (ref "C18") (pin "2") (pinfunction "2_2") (pintype "passive"))
      (node (ref "C2") (pin "2") (pinfunction "2_2") (pintype "passive"))
      (node (ref "C3") (pin "2") (pinfunction "2_2") (pintype "passive"))
      (node (ref "C30") (pin "2") (pinfunction "2_2") (pintype "passive"))
      (node (ref "C31") (pin "2") (pinfunction "2_2") (pintype "passive"))
      (node (ref "C32") (pin "2") (pinfunction "2_2") (pintype "passive"))
      (node (ref "D10") (pin "1") (pinfunction "A_1") (pintype "passive"))
      (node (ref "D5") (pin "1") (pinfunction "A_1") (pintype "passive"))
      (node (ref "L6932-1") (pin "4") (pinfunction "OUT_4") (pintype "power_in"))
      (node (ref "L6932-2") (pin "4") (pinfunction "OUT_4") (pintype "power_in"))
      (node (ref "R15") (pin "2") (pinfunction "2_2") (pintype "passive"))
      (node (ref "R5") (pin "2") (pinfunction "2_2") (pintype "passive"))
      (node (ref "R50") (pin "2") (pinfunction "2_2") (pintype "passive"))
      (node (ref "R6") (pin "2") (pinfunction "2_2") (pintype "passive"))
      (node (ref "R61") (pin "2") (pinfunction "2_2") (pintype "passive"))
      (node (ref "R7") (pin "2") (pinfunction "2_2") (pintype "passive"))
      (node (ref "R8") (pin "2") (pinfunction "2_2") (pintype "passive"))
      (node (ref "TLV2462_1") (pin "8") (pinfunction "VCC_8") (pintype "power_in"))
      (node (ref "TLV2462_2") (pin "8") (pinfunction "VCC_8") (pintype "power_in"))
      (node (ref "TLV2462_3") (pin "8") (pinfunction "VCC_8") (pintype "power_in"))
      (node (ref "oled") (pin "2") (pinfunction "3.3v_2") (pintype "power_in"))
      (node (ref "sdcard") (pin "4") (pinfunction "VDD_4") (pintype "power_in"))
      (node (ref "sensor_tuoluoyi") (pin "3") (pinfunction "3.3V_3") (pintype "power_in"))
      (node (ref "wifi") (pin "2") (pinfunction "3.3V_2") (pintype "power_in"))
    )
    (net (code "46") (name "5V") (class "Default")
      (node (ref "D6") (pin "1") (pinfunction "A_1") (pintype "passive"))
      (node (ref "F1") (pin "2") (pinfunction "2_2") (pintype "passive"))
      (node (ref "K60 144PIN V4.0系统板") (pin "432") (pinfunction "VCC_432") (pintype "passive"))
      (node (ref "R17") (pin "2") (pinfunction "2_2") (pintype "passive"))
      (node (ref "R18") (pin "2") (pinfunction "2_2") (pintype "passive"))
      (node (ref "R19") (pin "2") (pinfunction "2_2") (pintype "passive"))
      (node (ref "R20") (pin "2") (pinfunction "2_2") (pintype "passive"))
      (node (ref "omron_encoder_left") (pin "2") (pinfunction "5v_2") (pintype "power_in"))
      (node (ref "omron_encoder_right") (pin "2") (pinfunction "5v_2") (pintype "power_in"))
    )
    (net (code "47") (name "GND") (class "Default")
      (node (ref "BSS306N") (pin "1") (pinfunction "D_1") (pintype "passive"))
      (node (ref "BSS306N") (pin "3") (pinfunction "S_3") (pintype "passive"))
      (node (ref "C1") (pin "1") (pinfunction "1_1") (pintype "passive"))
      (node (ref "C10") (pin "2") (pinfunction "2_2") (pintype "passive"))
      (node (ref "C11") (pin "1") (pinfunction "1_1") (pintype "passive"))
      (node (ref "C12") (pin "2") (pinfunction "2_2") (pintype "passive"))
      (node (ref "C13") (pin "1") (pinfunction "1_1") (pintype "passive"))
      (node (ref "C14") (pin "1") (pinfunction "1_1") (pintype "passive"))
      (node (ref "C15") (pin "2") (pinfunction "2_2") (pintype "passive"))
      (node (ref "C16") (pin "1") (pinfunction "1_1") (pintype "passive"))
      (node (ref "C18") (pin "1") (pinfunction "1_1") (pintype "passive"))
      (node (ref "C3") (pin "1") (pinfunction "1_1") (pintype "passive"))
      (node (ref "C31") (pin "1") (pinfunction "1_1") (pintype "passive"))
      (node (ref "C32") (pin "1") (pinfunction "1_1") (pintype "passive"))
      (node (ref "C4") (pin "2") (pinfunction "2_2") (pintype "passive"))
      (node (ref "C5") (pin "2") (pinfunction "2_2") (pintype "passive"))
      (node (ref "C6") (pin "2") (pinfunction "2_2") (pintype "passive"))
      (node (ref "C7") (pin "2") (pinfunction "2_2") (pintype "passive"))
      (node (ref "C8") (pin "1") (pinfunction "1_1") (pintype "passive"))
      (node (ref "C9") (pin "1") (pinfunction "1_1") (pintype "passive"))
      (node (ref "CON1") (pin "1") (pinfunction "1_1") (pintype "passive"))
      (node (ref "K60 144PIN V4.0系统板") (pin "401") (pinfunction "GND_401") (pintype "passive"))
      (node (ref "L6932-1") (pin "5") (pinfunction "GND_5") (pintype "power_in"))
      (node (ref "L6932-1") (pin "6") (pinfunction "GND_6") (pintype "power_in"))
      (node (ref "L6932-1") (pin "7") (pinfunction "GND_7") (pintype "power_in"))
      (node (ref "L6932-1") (pin "8") (pinfunction "GND_8") (pintype "power_in"))
      (node (ref "L6932-2") (pin "5") (pinfunction "GND_5") (pintype "power_in"))
      (node (ref "L6932-2") (pin "6") (pinfunction "GND_6") (pintype "power_in"))
      (node (ref "L6932-2") (pin "7") (pinfunction "GND_7") (pintype "power_in"))
      (node (ref "L6932-2") (pin "8") (pinfunction "GND_8") (pintype "power_in"))
      (node (ref "LM1117-5") (pin "1") (pinfunction "GND_1") (pintype "power_in"))
      (node (ref "R1") (pin "1") (pinfunction "1_1") (pintype "passive"))
      (node (ref "R10") (pin "1") (pinfunction "1_1") (pintype "passive"))
      (node (ref "R16") (pin "1") (pinfunction "1_1") (pintype "passive"))
      (node (ref "R2") (pin "1") (pinfunction "1_1") (pintype "passive"))
      (node (ref "R27") (pin "1") (pinfunction "1_1") (pintype "passive"))
      (node (ref "R28") (pin "1") (pinfunction "1_1") (pintype "passive"))
      (node (ref "R29") (pin "1") (pinfunction "1_1") (pintype "passive"))
      (node (ref "R3") (pin "2") (pinfunction "2_2") (pintype "passive"))
      (node (ref "R30") (pin "1") (pinfunction "1_1") (pintype "passive"))
      (node (ref "R31") (pin "2") (pinfunction "2_2") (pintype "passive"))
      (node (ref "R4") (pin "2") (pinfunction "2_2") (pintype "passive"))
      (node (ref "R45") (pin "2") (pinfunction "2_2") (pintype "passive"))
      (node (ref "R47") (pin "1") (pinfunction "1_1") (pintype "passive"))
      (node (ref "R60") (pin "1") (pinfunction "1_1") (pintype "passive"))
      (node (ref "R62") (pin "1") (pinfunction "1_1") (pintype "passive"))
      (node (ref "S8") (pin "1") (pinfunction "1_1") (pintype "passive"))
      (node (ref "TLV2462_1") (pin "4") (pinfunction "GND_4") (pintype "power_in"))
      (node (ref "TLV2462_2") (pin "4") (pinfunction "GND_4") (pintype "power_in"))
      (node (ref "TLV2462_3") (pin "4") (pinfunction "GND_4") (pintype "power_in"))
      (node (ref "button1") (pin "2") (pinfunction "2_2") (pintype "passive"))
      (node (ref "button2") (pin "2") (pinfunction "2_2") (pintype "passive"))
      (node (ref "button3") (pin "2") (pinfunction "2_2") (pintype "passive"))
      (node (ref "button4") (pin "2") (pinfunction "2_2") (pintype "passive"))
      (node (ref "button5") (pin "2") (pinfunction "2_2") (pintype "passive"))
      (node (ref "button6") (pin "2") (pinfunction "2_2") (pintype "passive"))
      (node (ref "button7") (pin "2") (pinfunction "2_2") (pintype "passive"))
      (node (ref "oled") (pin "1") (pinfunction "GND_1") (pintype "passive"))
      (node (ref "omron_encoder_left") (pin "1") (pinfunction "GND_1") (pintype "power_in"))
      (node (ref "omron_encoder_right") (pin "1") (pinfunction "GND_1") (pintype "power_in"))
      (node (ref "pwm") (pin "1") (pinfunction "GND_1") (pintype "power_in"))
      (node (ref "sdcard") (pin "6") (pinfunction "VSS_6") (pintype "power_in"))
      (node (ref "sdcard") (pin "G1") (pinfunction "G1_G1") (pintype "power_in"))
      (node (ref "sdcard") (pin "G2") (pinfunction "G2_G2") (pintype "power_in"))
      (node (ref "sdcard") (pin "G3") (pinfunction "G3_G3") (pintype "power_in"))
      (node (ref "sdcard") (pin "G4") (pinfunction "G4_G4") (pintype "power_in"))
      (node (ref "sensor_tuoluoyi") (pin "4") (pinfunction "GND_4") (pintype "passive"))
      (node (ref "wifi") (pin "1") (pinfunction "GND_1") (pintype "power_in"))
    )
    (net (code "48") (name "Net-(BSS306N-G)") (class "Default")
      (node (ref "BSS306N") (pin "2") (pinfunction "G_2") (pintype "passive"))
      (node (ref "C16") (pin "2") (pinfunction "2_2") (pintype "passive"))
      (node (ref "C4") (pin "1") (pinfunction "1_1") (pintype "passive"))
      (node (ref "C5") (pin "1") (pinfunction "1_1") (pintype "passive"))
      (node (ref "CON1") (pin "2") (pinfunction "2_2") (pintype "passive"))
      (node (ref "L6932-1") (pin "1") (pinfunction "EN_1") (pintype "power_in"))
      (node (ref "L6932-1") (pin "2") (pinfunction "IN_2") (pintype "power_in"))
      (node (ref "L6932-2") (pin "1") (pinfunction "EN_1") (pintype "power_in"))
      (node (ref "L6932-2") (pin "2") (pinfunction "IN_2") (pintype "power_in"))
      (node (ref "LM1117-5") (pin "3") (pinfunction "VIN_3") (pintype "power_in"))
    )
    (net (code "49") (name "Net-(D5-K)") (class "Default")
      (node (ref "D5") (pin "2") (pinfunction "K_2") (pintype "passive"))
      (node (ref "R1") (pin "2") (pinfunction "2_2") (pintype "passive"))
    )
    (net (code "50") (name "Net-(D6-K)") (class "Default")
      (node (ref "D6") (pin "2") (pinfunction "K_2") (pintype "passive"))
      (node (ref "R2") (pin "2") (pinfunction "2_2") (pintype "passive"))
    )
    (net (code "51") (name "Net-(D10-K)") (class "Default")
      (node (ref "D10") (pin "2") (pinfunction "K_2") (pintype "passive"))
      (node (ref "R60") (pin "2") (pinfunction "2_2") (pintype "passive"))
    )
    (net (code "52") (name "Net-(L6932-1-ADJ)") (class "Default")
      (node (ref "C2") (pin "1") (pinfunction "1_1") (pintype "passive"))
      (node (ref "L6932-1") (pin "3") (pinfunction "ADJ_3") (pintype "power_in"))
      (node (ref "R15") (pin "1") (pinfunction "1_1") (pintype "passive"))
      (node (ref "R16") (pin "2") (pinfunction "2_2") (pintype "passive"))
    )
    (net (code "53") (name "Net-(L6932-2-ADJ)") (class "Default")
      (node (ref "C30") (pin "1") (pinfunction "1_1") (pintype "passive"))
      (node (ref "L6932-2") (pin "3") (pinfunction "ADJ_3") (pintype "power_in"))
      (node (ref "R61") (pin "1") (pinfunction "1_1") (pintype "passive"))
      (node (ref "R62") (pin "2") (pinfunction "2_2") (pintype "passive"))
    )
    (net (code "54") (name "Net-(LM1117-5-VOUT)") (class "Default")
      (node (ref "C6") (pin "1") (pinfunction "1_1") (pintype "passive"))
      (node (ref "C7") (pin "1") (pinfunction "1_1") (pintype "passive"))
      (node (ref "F1") (pin "1") (pinfunction "1_1") (pintype "passive"))
      (node (ref "LM1117-5") (pin "2") (pinfunction "VOUT_2") (pintype "power_in"))
    )
    (net (code "55") (name "Net-(R9-Pad2)") (class "Default")
      (node (ref "R9") (pin "2") (pinfunction "2_2") (pintype "passive"))
      (node (ref "TLV2462_3") (pin "5") (pinfunction "5_5") (pintype "input"))
    )
    (net (code "56") (name "Net-(R10-Pad2)") (class "Default")
      (node (ref "R10") (pin "2") (pinfunction "2_2") (pintype "passive"))
      (node (ref "R11") (pin "1") (pinfunction "1_1") (pintype "passive"))
      (node (ref "TLV2462_3") (pin "6") (pinfunction "6_6") (pintype "input"))
    )
    (net (code "57") (name "Net-(R13-BOT)") (class "Default")
      (node (ref "R11") (pin "2") (pinfunction "2_2") (pintype "passive"))
      (node (ref "R13") (pin "2") (pinfunction "BOT_2") (pintype "passive"))
    )
    (net (code "58") (name "Net-(R13-TAP)") (class "Default")
      (node (ref "R12") (pin "1") (pinfunction "1_1") (pintype "passive"))
      (node (ref "R13") (pin "1") (pinfunction "TOP_1") (pintype "passive"))
      (node (ref "R13") (pin "3") (pinfunction "TAP_3") (pintype "passive"))
      (node (ref "TLV2462_3") (pin "7") (pinfunction "7_7") (pintype "output"))
    )
    (net (code "59") (name "Net-(R21-Pad2)") (class "Default")
      (node (ref "R21") (pin "2") (pinfunction "2_2") (pintype "passive"))
      (node (ref "TLV2462_3") (pin "3") (pinfunction "3_3") (pintype "input"))
    )
    (net (code "60") (name "Net-(R24-Pad2)") (class "Default")
      (node (ref "R24") (pin "2") (pinfunction "2_2") (pintype "passive"))
      (node (ref "TLV2462_2") (pin "5") (pinfunction "5_5") (pintype "input"))
    )
    (net (code "61") (name "Net-(R25-Pad2)") (class "Default")
      (node (ref "R25") (pin "2") (pinfunction "2_2") (pintype "passive"))
      (node (ref "TLV2462_2") (pin "3") (pinfunction "3_3") (pintype "input"))
    )
    (net (code "62") (name "Net-(R26-Pad2)") (class "Default")
      (node (ref "R26") (pin "2") (pinfunction "2_2") (pintype "passive"))
      (node (ref "TLV2462_1") (pin "5") (pinfunction "5_5") (pintype "input"))
    )
    (net (code "63") (name "Net-(R27-Pad2)") (class "Default")
      (node (ref "R27") (pin "2") (pinfunction "2_2") (pintype "passive"))
      (node (ref "R32") (pin "1") (pinfunction "1_1") (pintype "passive"))
      (node (ref "TLV2462_3") (pin "2") (pinfunction "2_2") (pintype "input"))
    )
    (net (code "64") (name "Net-(R28-Pad2)") (class "Default")
      (node (ref "R28") (pin "2") (pinfunction "2_2") (pintype "passive"))
      (node (ref "R33") (pin "1") (pinfunction "1_1") (pintype "passive"))
      (node (ref "TLV2462_2") (pin "6") (pinfunction "6_6") (pintype "input"))
    )
    (net (code "65") (name "Net-(R29-Pad2)") (class "Default")
      (node (ref "R29") (pin "2") (pinfunction "2_2") (pintype "passive"))
      (node (ref "R34") (pin "1") (pinfunction "1_1") (pintype "passive"))
      (node (ref "TLV2462_2") (pin "2") (pinfunction "2_2") (pintype "input"))
    )
    (net (code "66") (name "Net-(R30-Pad2)") (class "Default")
      (node (ref "R30") (pin "2") (pinfunction "2_2") (pintype "passive"))
      (node (ref "R36") (pin "1") (pinfunction "1_1") (pintype "passive"))
      (node (ref "TLV2462_1") (pin "2") (pinfunction "2_2") (pintype "input"))
    )
    (net (code "67") (name "Net-(R35-Pad1)") (class "Default")
      (node (ref "R35") (pin "1") (pinfunction "1_1") (pintype "passive"))
      (node (ref "R47") (pin "2") (pinfunction "2_2") (pintype "passive"))
      (node (ref "TLV2462_1") (pin "6") (pinfunction "6_6") (pintype "input"))
    )
    (net (code "68") (name "Net-(R41-BOT)") (class "Default")
      (node (ref "R32") (pin "2") (pinfunction "2_2") (pintype "passive"))
      (node (ref "R41") (pin "2") (pinfunction "BOT_2") (pintype "passive"))
    )
    (net (code "69") (name "Net-(R41-TAP)") (class "Default")
      (node (ref "R37") (pin "1") (pinfunction "1_1") (pintype "passive"))
      (node (ref "R41") (pin "1") (pinfunction "TOP_1") (pintype "passive"))
      (node (ref "R41") (pin "3") (pinfunction "TAP_3") (pintype "passive"))
      (node (ref "TLV2462_3") (pin "1") (pinfunction "1_1") (pintype "output"))
    )
    (net (code "70") (name "Net-(R42-BOT)") (class "Default")
      (node (ref "R33") (pin "2") (pinfunction "2_2") (pintype "passive"))
      (node (ref "R42") (pin "2") (pinfunction "BOT_2") (pintype "passive"))
    )
    (net (code "71") (name "Net-(R42-TAP)") (class "Default")
      (node (ref "R38") (pin "1") (pinfunction "1_1") (pintype "passive"))
      (node (ref "R42") (pin "1") (pinfunction "TOP_1") (pintype "passive"))
      (node (ref "R42") (pin "3") (pinfunction "TAP_3") (pintype "passive"))
      (node (ref "TLV2462_2") (pin "7") (pinfunction "7_7") (pintype "output"))
    )
    (net (code "72") (name "Net-(R43-BOT)") (class "Default")
      (node (ref "R35") (pin "2") (pinfunction "2_2") (pintype "passive"))
      (node (ref "R43") (pin "2") (pinfunction "BOT_2") (pintype "passive"))
    )
    (net (code "73") (name "Net-(R43-TAP)") (class "Default")
      (node (ref "R43") (pin "1") (pinfunction "TOP_1") (pintype "passive"))
      (node (ref "R43") (pin "3") (pinfunction "TAP_3") (pintype "passive"))
      (node (ref "R48") (pin "1") (pinfunction "1_1") (pintype "passive"))
      (node (ref "TLV2462_1") (pin "7") (pinfunction "7_7") (pintype "output"))
    )
    (net (code "74") (name "Net-(R44-BOT)") (class "Default")
      (node (ref "R36") (pin "2") (pinfunction "2_2") (pintype "passive"))
      (node (ref "R44") (pin "2") (pinfunction "BOT_2") (pintype "passive"))
    )
    (net (code "75") (name "Net-(R44-TAP)") (class "Default")
      (node (ref "R40") (pin "1") (pinfunction "1_1") (pintype "passive"))
      (node (ref "R44") (pin "1") (pinfunction "TOP_1") (pintype "passive"))
      (node (ref "R44") (pin "3") (pinfunction "TAP_3") (pintype "passive"))
      (node (ref "TLV2462_1") (pin "1") (pinfunction "1_1") (pintype "output"))
    )
    (net (code "76") (name "Net-(R46-Pad2)") (class "Default")
      (node (ref "R46") (pin "2") (pinfunction "2_2") (pintype "passive"))
      (node (ref "TLV2462_1") (pin "3") (pinfunction "3_3") (pintype "input"))
    )
    (net (code "77") (name "Net-(R49-BOT)") (class "Default")
      (node (ref "R34") (pin "2") (pinfunction "2_2") (pintype "passive"))
      (node (ref "R49") (pin "2") (pinfunction "BOT_2") (pintype "passive"))
    )
    (net (code "78") (name "Net-(R49-TAP)") (class "Default")
      (node (ref "R39") (pin "1") (pinfunction "1_1") (pintype "passive"))
      (node (ref "R49") (pin "1") (pinfunction "TOP_1") (pintype "passive"))
      (node (ref "R49") (pin "3") (pinfunction "TAP_3") (pintype "passive"))
      (node (ref "TLV2462_2") (pin "1") (pinfunction "1_1") (pintype "output"))
    )
    (net (code "79") (name "Net-(wifi-RESET)") (class "Default")
      (node (ref "R50") (pin "1") (pinfunction "1_1") (pintype "passive"))
      (node (ref "S8") (pin "2") (pinfunction "2_2") (pintype "passive"))
      (node (ref "wifi") (pin "7") (pinfunction "RESET_7") (pintype "power_in"))
    )
    (net (code "80") (name "unconnected-(C10-Pad1)") (class "Default")
      (node (ref "C10") (pin "1") (pinfunction "1_1") (pintype "passive"))
    )
    (net (code "81") (name "unconnected-(C12-Pad1)") (class "Default")
      (node (ref "C12") (pin "1") (pinfunction "1_1") (pintype "passive"))
    )
    (net (code "82") (name "unconnected-(C15-Pad1)") (class "Default")
      (node (ref "C15") (pin "1") (pinfunction "1_1") (pintype "passive"))
    )
    (net (code "83") (name "unconnected-(K60 144PIN V4.0系统板-ADC0_SE16-Pad130)") (class "Default")
      (node (ref "K60 144PIN V4.0系统板") (pin "130") (pinfunction "ADC0_SE16_130") (pintype "passive"))
    )
    (net (code "84") (name "unconnected-(K60 144PIN V4.0系统板-ADC0_SE23-Pad301)") (class "Default")
      (node (ref "K60 144PIN V4.0系统板") (pin "301") (pinfunction "ADC0_SE23_301") (pintype "passive"))
    )
    (net (code "85") (name "unconnected-(K60 144PIN V4.0系统板-ADC1_SE16-Pad129)") (class "Default")
      (node (ref "K60 144PIN V4.0系统板") (pin "129") (pinfunction "ADC1_SE16_129") (pintype "passive"))
    )
    (net (code "86") (name "unconnected-(K60 144PIN V4.0系统板-ADC1_SE23-Pad303)") (class "Default")
      (node (ref "K60 144PIN V4.0系统板") (pin "303") (pinfunction "ADC1_SE23_303") (pintype "passive"))
    )
    (net (code "87") (name "unconnected-(K60 144PIN V4.0系统板-GND-Pad304)") (class "Default")
      (node (ref "K60 144PIN V4.0系统板") (pin "304") (pinfunction "GND_304") (pintype "passive"))
    )
    (net (code "88") (name "unconnected-(K60 144PIN V4.0系统板-GND-Pad305)") (class "Default")
      (node (ref "K60 144PIN V4.0系统板") (pin "305") (pinfunction "GND_305") (pintype "passive"))
    )
    (net (code "89") (name "unconnected-(K60 144PIN V4.0系统板-GND-Pad312)") (class "Default")
      (node (ref "K60 144PIN V4.0系统板") (pin "312") (pinfunction "GND_312") (pintype "passive"))
    )
    (net (code "90") (name "unconnected-(K60 144PIN V4.0系统板-GND-Pad313)") (class "Default")
      (node (ref "K60 144PIN V4.0系统板") (pin "313") (pinfunction "GND_313") (pintype "passive"))
    )
    (net (code "91") (name "unconnected-(K60 144PIN V4.0系统板-GND-Pad314)") (class "Default")
      (node (ref "K60 144PIN V4.0系统板") (pin "314") (pinfunction "GND_314") (pintype "passive"))
    )
    (net (code "92") (name "unconnected-(K60 144PIN V4.0系统板-GND-Pad315)") (class "Default")
      (node (ref "K60 144PIN V4.0系统板") (pin "315") (pinfunction "GND_315") (pintype "passive"))
    )
    (net (code "93") (name "unconnected-(K60 144PIN V4.0系统板-GND-Pad331)") (class "Default")
      (node (ref "K60 144PIN V4.0系统板") (pin "331") (pinfunction "GND_331") (pintype "passive"))
    )
    (net (code "94") (name "unconnected-(K60 144PIN V4.0系统板-GND-Pad332)") (class "Default")
      (node (ref "K60 144PIN V4.0系统板") (pin "332") (pinfunction "GND_332") (pintype "passive"))
    )
    (net (code "95") (name "unconnected-(K60 144PIN V4.0系统板-GND-Pad402)") (class "Default")
      (node (ref "K60 144PIN V4.0系统板") (pin "402") (pinfunction "GND_402") (pintype "passive"))
    )
    (net (code "96") (name "unconnected-(K60 144PIN V4.0系统板-PGA0_DM-Pad126)") (class "Default")
      (node (ref "K60 144PIN V4.0系统板") (pin "126") (pinfunction "PGA0_DM_126") (pintype "passive"))
    )
    (net (code "97") (name "unconnected-(K60 144PIN V4.0系统板-PGA0_PM-Pad125)") (class "Default")
      (node (ref "K60 144PIN V4.0系统板") (pin "125") (pinfunction "PGA0_PM_125") (pintype "passive"))
    )
    (net (code "98") (name "unconnected-(K60 144PIN V4.0系统板-PGA1_DM-Pad128)") (class "Default")
      (node (ref "K60 144PIN V4.0系统板") (pin "128") (pinfunction "PGA1_DM_128") (pintype "passive"))
    )
    (net (code "99") (name "unconnected-(K60 144PIN V4.0系统板-PGA1_PM-Pad127)") (class "Default")
      (node (ref "K60 144PIN V4.0系统板") (pin "127") (pinfunction "PGA1_PM_127") (pintype "passive"))
    )
    (net (code "100") (name "unconnected-(K60 144PIN V4.0系统板-PGA2_DM-Pad122)") (class "Default")
      (node (ref "K60 144PIN V4.0系统板") (pin "122") (pinfunction "PGA2_DM_122") (pintype "passive"))
    )
    (net (code "101") (name "unconnected-(K60 144PIN V4.0系统板-PGA2_DP-Pad121)") (class "Default")
      (node (ref "K60 144PIN V4.0系统板") (pin "121") (pinfunction "PGA2_DP_121") (pintype "passive"))
    )
    (net (code "102") (name "unconnected-(K60 144PIN V4.0系统板-PGA3_DM-Pad124)") (class "Default")
      (node (ref "K60 144PIN V4.0系统板") (pin "124") (pinfunction "PGA3_DM_124") (pintype "passive"))
    )
    (net (code "103") (name "unconnected-(K60 144PIN V4.0系统板-PGA3_PM-Pad123)") (class "Default")
      (node (ref "K60 144PIN V4.0系统板") (pin "123") (pinfunction "PGA3_PM_123") (pintype "passive"))
    )
    (net (code "104") (name "unconnected-(K60 144PIN V4.0系统板-PTA4-Pad316)") (class "Default")
      (node (ref "K60 144PIN V4.0系统板") (pin "316") (pinfunction "PTA4_316") (pintype "passive"))
    )
    (net (code "105") (name "unconnected-(K60 144PIN V4.0系统板-PTA5-Pad317)") (class "Default")
      (node (ref "K60 144PIN V4.0系统板") (pin "317") (pinfunction "PTA5_317") (pintype "passive"))
    )
    (net (code "106") (name "unconnected-(K60 144PIN V4.0系统板-PTA6-Pad318)") (class "Default")
      (node (ref "K60 144PIN V4.0系统板") (pin "318") (pinfunction "PTA6_318") (pintype "passive"))
    )
    (net (code "107") (name "unconnected-(K60 144PIN V4.0系统板-PTA7-Pad319)") (class "Default")
      (node (ref "K60 144PIN V4.0系统板") (pin "319") (pinfunction "PTA7_319") (pintype "passive"))
    )
    (net (code "108") (name "unconnected-(K60 144PIN V4.0系统板-PTA8-Pad320)") (class "Default")
      (node (ref "K60 144PIN V4.0系统板") (pin "320") (pinfunction "PTA8_320") (pintype "passive"))
    )
    (net (code "109") (name "unconnected-(K60 144PIN V4.0系统板-PTA9-Pad321)") (class "Default")
      (node (ref "K60 144PIN V4.0系统板") (pin "321") (pinfunction "PTA9_321") (pintype "passive"))
    )
    (net (code "110") (name "unconnected-(K60 144PIN V4.0系统板-PTA16-Pad328)") (class "Default")
      (node (ref "K60 144PIN V4.0系统板") (pin "328") (pinfunction "PTA16_328") (pintype "passive"))
    )
    (net (code "111") (name "unconnected-(K60 144PIN V4.0系统板-PTA17-Pad329)") (class "Default")
      (node (ref "K60 144PIN V4.0系统板") (pin "329") (pinfunction "PTA17_329") (pintype "passive"))
    )
    (net (code "112") (name "unconnected-(K60 144PIN V4.0系统板-PTA19-Pad330)") (class "Default")
      (node (ref "K60 144PIN V4.0系统板") (pin "330") (pinfunction "PTA19_330") (pintype "passive"))
    )
    (net (code "113") (name "unconnected-(K60 144PIN V4.0系统板-PTA24-Pad229)") (class "Default")
      (node (ref "K60 144PIN V4.0系统板") (pin "229") (pinfunction "PTA24_229") (pintype "passive"))
    )
    (net (code "114") (name "unconnected-(K60 144PIN V4.0系统板-PTA25-Pad230)") (class "Default")
      (node (ref "K60 144PIN V4.0系统板") (pin "230") (pinfunction "PTA25_230") (pintype "passive"))
    )
    (net (code "115") (name "unconnected-(K60 144PIN V4.0系统板-PTA26-Pad227)") (class "Default")
      (node (ref "K60 144PIN V4.0系统板") (pin "227") (pinfunction "PTA26_227") (pintype "passive"))
    )
    (net (code "116") (name "unconnected-(K60 144PIN V4.0系统板-PTA27-Pad228)") (class "Default")
      (node (ref "K60 144PIN V4.0系统板") (pin "228") (pinfunction "PTA27_228") (pintype "passive"))
    )
    (net (code "117") (name "unconnected-(K60 144PIN V4.0系统板-PTA28-Pad225)") (class "Default")
      (node (ref "K60 144PIN V4.0系统板") (pin "225") (pinfunction "PTA28_225") (pintype "passive"))
    )
    (net (code "118") (name "unconnected-(K60 144PIN V4.0系统板-PTA29-Pad226)") (class "Default")
      (node (ref "K60 144PIN V4.0系统板") (pin "226") (pinfunction "PTA29_226") (pintype "passive"))
    )
    (net (code "119") (name "unconnected-(K60 144PIN V4.0系统板-PTB0-Pad223)") (class "Default")
      (node (ref "K60 144PIN V4.0系统板") (pin "223") (pinfunction "PTB0_223") (pintype "passive"))
    )
    (net (code "120") (name "unconnected-(K60 144PIN V4.0系统板-PTB2-Pad221)") (class "Default")
      (node (ref "K60 144PIN V4.0系统板") (pin "221") (pinfunction "PTB2_221") (pintype "passive"))
    )
    (net (code "121") (name "unconnected-(K60 144PIN V4.0系统板-PTB3-Pad222)") (class "Default")
      (node (ref "K60 144PIN V4.0系统板") (pin "222") (pinfunction "PTB3_222") (pintype "passive"))
    )
    (net (code "122") (name "unconnected-(K60 144PIN V4.0系统板-PTB8-Pad215)") (class "Default")
      (node (ref "K60 144PIN V4.0系统板") (pin "215") (pinfunction "PTB8_215") (pintype "passive"))
    )
    (net (code "123") (name "unconnected-(K60 144PIN V4.0系统板-PTB9-Pad216)") (class "Default")
      (node (ref "K60 144PIN V4.0系统板") (pin "216") (pinfunction "PTB9_216") (pintype "passive"))
    )
    (net (code "124") (name "unconnected-(K60 144PIN V4.0系统板-PTB11-Pad214)") (class "Default")
      (node (ref "K60 144PIN V4.0系统板") (pin "214") (pinfunction "PTB11_214") (pintype "passive"))
    )
    (net (code "125") (name "unconnected-(K60 144PIN V4.0系统板-PTB16-Pad211)") (class "Default")
      (node (ref "K60 144PIN V4.0系统板") (pin "211") (pinfunction "PTB16_211") (pintype "passive"))
    )
    (net (code "126") (name "unconnected-(K60 144PIN V4.0系统板-PTB17-Pad212)") (class "Default")
      (node (ref "K60 144PIN V4.0系统板") (pin "212") (pinfunction "PTB17_212") (pintype "passive"))
    )
    (net (code "127") (name "unconnected-(K60 144PIN V4.0系统板-PTB18-Pad209)") (class "Default")
      (node (ref "K60 144PIN V4.0系统板") (pin "209") (pinfunction "PTB18_209") (pintype "passive"))
    )
    (net (code "128") (name "unconnected-(K60 144PIN V4.0系统板-PTB19-Pad210)") (class "Default")
      (node (ref "K60 144PIN V4.0系统板") (pin "210") (pinfunction "PTB19_210") (pintype "passive"))
    )
    (net (code "129") (name "unconnected-(K60 144PIN V4.0系统板-PTB20-Pad207)") (class "Default")
      (node (ref "K60 144PIN V4.0系统板") (pin "207") (pinfunction "PTB20_207") (pintype "passive"))
    )
    (net (code "130") (name "unconnected-(K60 144PIN V4.0系统板-PTB21-Pad208)") (class "Default")
      (node (ref "K60 144PIN V4.0系统板") (pin "208") (pinfunction "PTB21_208") (pintype "passive"))
    )
    (net (code "131") (name "unconnected-(K60 144PIN V4.0系统板-PTB22-Pad205)") (class "Default")
      (node (ref "K60 144PIN V4.0系统板") (pin "205") (pinfunction "PTB22_205") (pintype "passive"))
    )
    (net (code "132") (name "unconnected-(K60 144PIN V4.0系统板-PTB23-Pad206)") (class "Default")
      (node (ref "K60 144PIN V4.0系统板") (pin "206") (pinfunction "PTB23_206") (pintype "passive"))
    )
    (net (code "133") (name "unconnected-(K60 144PIN V4.0系统板-PTC0-Pad203)") (class "Default")
      (node (ref "K60 144PIN V4.0系统板") (pin "203") (pinfunction "PTC0_203") (pintype "passive"))
    )
    (net (code "134") (name "unconnected-(K60 144PIN V4.0系统板-PTC3-Pad202)") (class "Default")
      (node (ref "K60 144PIN V4.0系统板") (pin "202") (pinfunction "PTC3_202") (pintype "passive"))
    )
    (net (code "135") (name "unconnected-(K60 144PIN V4.0系统板-PTD0-Pad413)") (class "Default")
      (node (ref "K60 144PIN V4.0系统板") (pin "413") (pinfunction "PTD0_413") (pintype "passive"))
    )
    (net (code "136") (name "unconnected-(K60 144PIN V4.0系统板-PTD1-Pad414)") (class "Default")
      (node (ref "K60 144PIN V4.0系统板") (pin "414") (pinfunction "PTD1_414") (pintype "passive"))
    )
    (net (code "137") (name "unconnected-(K60 144PIN V4.0系统板-PTD2-Pad411)") (class "Default")
      (node (ref "K60 144PIN V4.0系统板") (pin "411") (pinfunction "PTD2_411") (pintype "passive"))
    )
    (net (code "138") (name "unconnected-(K60 144PIN V4.0系统板-PTD3-Pad412)") (class "Default")
      (node (ref "K60 144PIN V4.0系统板") (pin "412") (pinfunction "PTD3_412") (pintype "passive"))
    )
    (net (code "139") (name "unconnected-(K60 144PIN V4.0系统板-PTD6-Pad407)") (class "Default")
      (node (ref "K60 144PIN V4.0系统板") (pin "407") (pinfunction "PTD6_407") (pintype "passive"))
    )
    (net (code "140") (name "unconnected-(K60 144PIN V4.0系统板-PTD7-Pad408)") (class "Default")
      (node (ref "K60 144PIN V4.0系统板") (pin "408") (pinfunction "PTD7_408") (pintype "passive"))
    )
    (net (code "141") (name "unconnected-(K60 144PIN V4.0系统板-PTD8-Pad405)") (class "Default")
      (node (ref "K60 144PIN V4.0系统板") (pin "405") (pinfunction "PTD8_405") (pintype "passive"))
    )
    (net (code "142") (name "unconnected-(K60 144PIN V4.0系统板-PTD9-Pad406)") (class "Default")
      (node (ref "K60 144PIN V4.0系统板") (pin "406") (pinfunction "PTD9_406") (pintype "passive"))
    )
    (net (code "143") (name "unconnected-(K60 144PIN V4.0系统板-PTD10-Pad403)") (class "Default")
      (node (ref "K60 144PIN V4.0系统板") (pin "403") (pinfunction "PTD10_403") (pintype "passive"))
    )
    (net (code "144") (name "unconnected-(K60 144PIN V4.0系统板-PTD11-Pad404)") (class "Default")
      (node (ref "K60 144PIN V4.0系统板") (pin "404") (pinfunction "PTD11_404") (pintype "passive"))
    )
    (net (code "145") (name "unconnected-(K60 144PIN V4.0系统板-PTD12-Pad101)") (class "Default")
      (node (ref "K60 144PIN V4.0系统板") (pin "101") (pinfunction "PTD12_101") (pintype "passive"))
    )
    (net (code "146") (name "unconnected-(K60 144PIN V4.0系统板-PTD13-Pad102)") (class "Default")
      (node (ref "K60 144PIN V4.0系统板") (pin "102") (pinfunction "PTD13_102") (pintype "passive"))
    )
    (net (code "147") (name "unconnected-(K60 144PIN V4.0系统板-PTD14-Pad103)") (class "Default")
      (node (ref "K60 144PIN V4.0系统板") (pin "103") (pinfunction "PTD14_103") (pintype "passive"))
    )
    (net (code "148") (name "unconnected-(K60 144PIN V4.0系统板-PTD15-Pad104)") (class "Default")
      (node (ref "K60 144PIN V4.0系统板") (pin "104") (pinfunction "PTD15_104") (pintype "passive"))
    )
    (net (code "149") (name "unconnected-(K60 144PIN V4.0系统板-PTE4-Pad109)") (class "Default")
      (node (ref "K60 144PIN V4.0系统板") (pin "109") (pinfunction "PTE4_109") (pintype "passive"))
    )
    (net (code "150") (name "unconnected-(K60 144PIN V4.0系统板-PTE5-Pad110)") (class "Default")
      (node (ref "K60 144PIN V4.0系统板") (pin "110") (pinfunction "PTE5_110") (pintype "passive"))
    )
    (net (code "151") (name "unconnected-(K60 144PIN V4.0系统板-PTE6-Pad111)") (class "Default")
      (node (ref "K60 144PIN V4.0系统板") (pin "111") (pinfunction "PTE6_111") (pintype "passive"))
    )
    (net (code "152") (name "unconnected-(K60 144PIN V4.0系统板-PTE7-Pad112)") (class "Default")
      (node (ref "K60 144PIN V4.0系统板") (pin "112") (pinfunction "PTE7_112") (pintype "passive"))
    )
    (net (code "153") (name "unconnected-(K60 144PIN V4.0系统板-PTE8-Pad113)") (class "Default")
      (node (ref "K60 144PIN V4.0系统板") (pin "113") (pinfunction "PTE8_113") (pintype "passive"))
    )
    (net (code "154") (name "unconnected-(K60 144PIN V4.0系统板-PTE9-Pad114)") (class "Default")
      (node (ref "K60 144PIN V4.0系统板") (pin "114") (pinfunction "PTE9_114") (pintype "passive"))
    )
    (net (code "155") (name "unconnected-(K60 144PIN V4.0系统板-PTE10-Pad115)") (class "Default")
      (node (ref "K60 144PIN V4.0系统板") (pin "115") (pinfunction "PTE10_115") (pintype "passive"))
    )
    (net (code "156") (name "unconnected-(K60 144PIN V4.0系统板-PTE11-Pad116)") (class "Default")
      (node (ref "K60 144PIN V4.0系统板") (pin "116") (pinfunction "PTE11_116") (pintype "passive"))
    )
    (net (code "157") (name "unconnected-(K60 144PIN V4.0系统板-PTE12-Pad117)") (class "Default")
      (node (ref "K60 144PIN V4.0系统板") (pin "117") (pinfunction "PTE12_117") (pintype "passive"))
    )
    (net (code "158") (name "unconnected-(K60 144PIN V4.0系统板-PTE25-Pad308)") (class "Default")
      (node (ref "K60 144PIN V4.0系统板") (pin "308") (pinfunction "PTE25_308") (pintype "passive"))
    )
    (net (code "159") (name "unconnected-(K60 144PIN V4.0系统板-PTE26-Pad309)") (class "Default")
      (node (ref "K60 144PIN V4.0系统板") (pin "309") (pinfunction "PTE26_309") (pintype "passive"))
    )
    (net (code "160") (name "unconnected-(K60 144PIN V4.0系统板-PTE27-Pad310)") (class "Default")
      (node (ref "K60 144PIN V4.0系统板") (pin "310") (pinfunction "PTE27_310") (pintype "passive"))
    )
    (net (code "161") (name "unconnected-(K60 144PIN V4.0系统板-PTE28-Pad311)") (class "Default")
      (node (ref "K60 144PIN V4.0系统板") (pin "311") (pinfunction "PTE28_311") (pintype "passive"))
    )
    (net (code "162") (name "unconnected-(K60 144PIN V4.0系统板-USB0_DM-Pad119)") (class "Default")
      (node (ref "K60 144PIN V4.0系统板") (pin "119") (pinfunction "USB0_DM_119") (pintype "passive"))
    )
    (net (code "163") (name "unconnected-(K60 144PIN V4.0系统板-USB0_DP-Pad118)") (class "Default")
      (node (ref "K60 144PIN V4.0系统板") (pin "118") (pinfunction "USB0_DP_118") (pintype "passive"))
    )
    (net (code "164") (name "unconnected-(K60 144PIN V4.0系统板-USB5V-Pad302)") (class "Default")
      (node (ref "K60 144PIN V4.0系统板") (pin "302") (pinfunction "USB5V_302") (pintype "passive"))
    )
    (net (code "165") (name "unconnected-(K60 144PIN V4.0系统板-VBAT-Pad306)") (class "Default")
      (node (ref "K60 144PIN V4.0系统板") (pin "306") (pinfunction "VBAT_306") (pintype "passive"))
    )
    (net (code "166") (name "unconnected-(K60 144PIN V4.0系统板-VCC-Pad431)") (class "Default")
      (node (ref "K60 144PIN V4.0系统板") (pin "431") (pinfunction "VCC_431") (pintype "passive"))
    )
    (net (code "167") (name "unconnected-(K60 144PIN V4.0系统板-VOUT33-Pad120)") (class "Default")
      (node (ref "K60 144PIN V4.0系统板") (pin "120") (pinfunction "VOUT33_120") (pintype "passive"))
    )
    (net (code "168") (name "unconnected-(sdcard-CDN-Pad9)") (class "Default")
      (node (ref "sdcard") (pin "9") (pinfunction "CDN_9") (pintype "power_in"))
    )
    (net (code "169") (name "unconnected-(sdcard-DATA1-Pad8)") (class "Default")
      (node (ref "sdcard") (pin "8") (pinfunction "DATA1_8") (pintype "power_in"))
    )
    (net (code "170") (name "unconnected-(sdcard-DATA2-Pad1)") (class "Default")
      (node (ref "sdcard") (pin "1") (pinfunction "DATA2_1") (pintype "power_in"))
    )
    (net (code "171") (name "unconnected-(wifi-PHY_RX+-Pad11)") (class "Default")
      (node (ref "wifi") (pin "11") (pinfunction "PHY_RX+_11") (pintype "power_in"))
    )
    (net (code "172") (name "unconnected-(wifi-PHY_RX--Pad12)") (class "Default")
      (node (ref "wifi") (pin "12") (pinfunction "PHY_RX-_12") (pintype "power_in"))
    )
    (net (code "173") (name "unconnected-(wifi-PHY_TX+-Pad13)") (class "Default")
      (node (ref "wifi") (pin "13") (pinfunction "PHY_TX+_13") (pintype "power_in"))
    )
    (net (code "174") (name "unconnected-(wifi-PHY_TX--Pad14)") (class "Default")
      (node (ref "wifi") (pin "14") (pinfunction "PHY_TX-_14") (pintype "power_in"))
    )
    (net (code "175") (name "unconnected-(wifi-UART_CTS-Pad6)") (class "Default")
      (node (ref "wifi") (pin "6") (pinfunction "UART_CTS_6") (pintype "power_in"))
    )
    (net (code "176") (name "unconnected-(wifi-UART_RTS-Pad5)") (class "Default")
      (node (ref "wifi") (pin "5") (pinfunction "UART_RTS_5") (pintype "power_in"))
    )
    (net (code "177") (name "unconnected-(wifi-nLink-Pad8)") (class "Default")
      (node (ref "wifi") (pin "8") (pinfunction "nLink_8") (pintype "power_in"))
    )
    (net (code "178") (name "unconnected-(wifi-nREADY-Pad9)") (class "Default")
      (node (ref "wifi") (pin "9") (pinfunction "nREADY_9") (pintype "power_in"))
    )
    (net (code "179") (name "unconnected-(wifi-nReload-Pad10)") (class "Default")
      (node (ref "wifi") (pin "10") (pinfunction "nReload_10") (pintype "power_in"))
    )
  )
)
